# Sheet1.net
KiCad netlist of a schematic drawn in Altium Designer
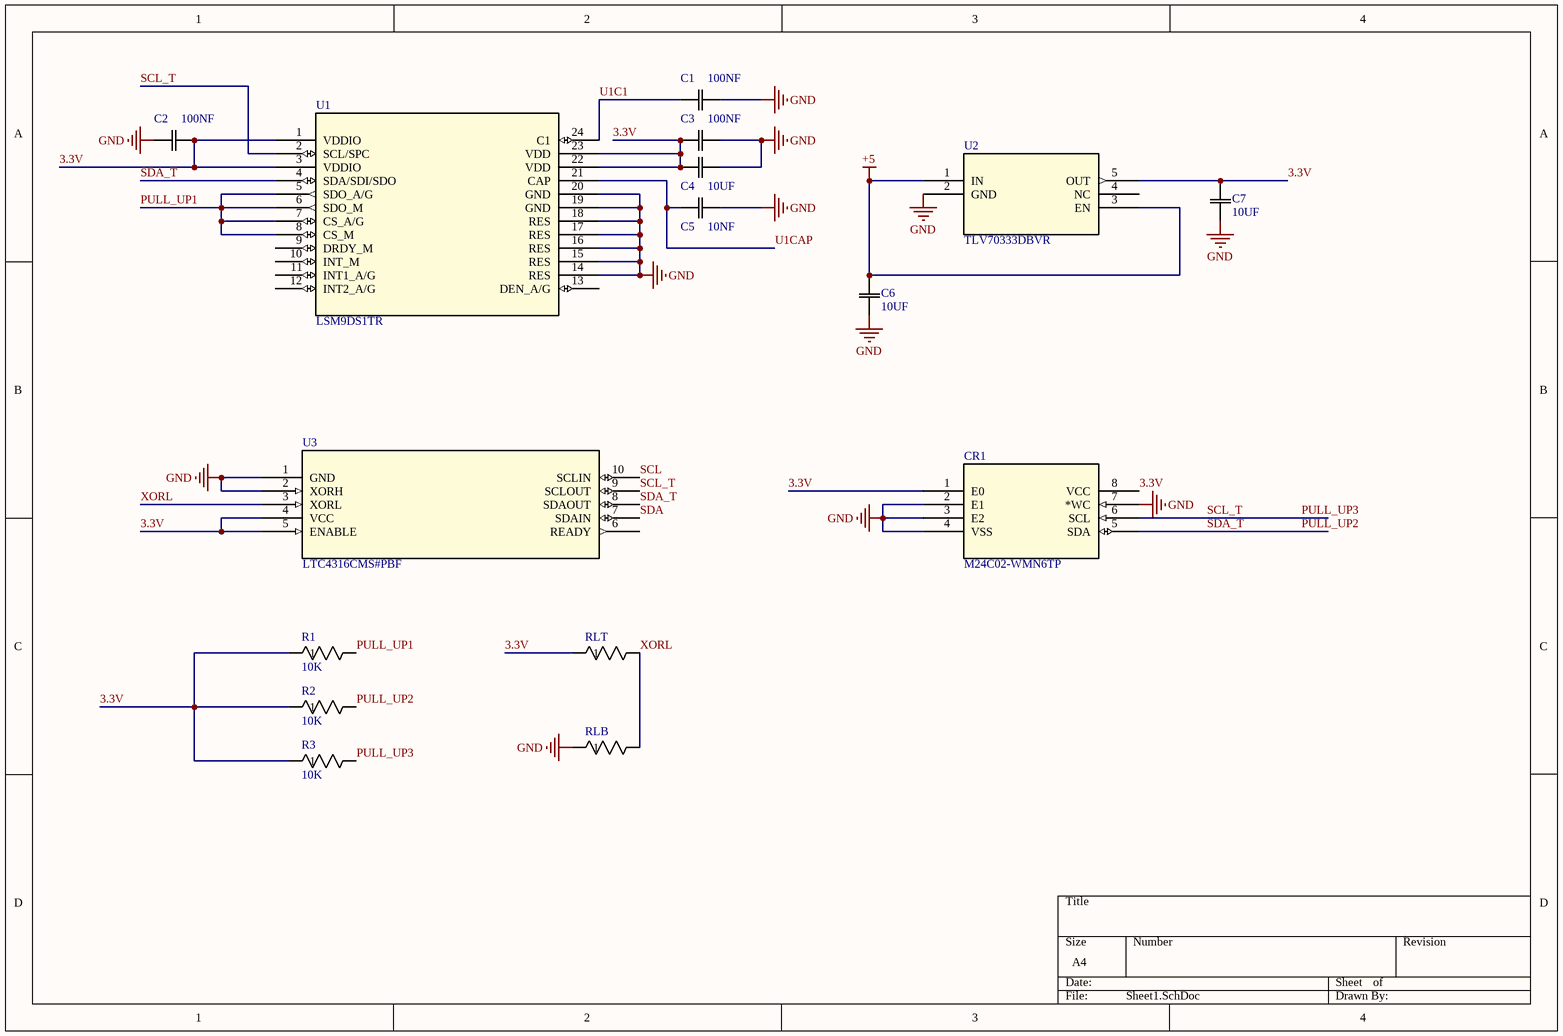
[diagram p0: Sheet1.SchDoc]

(export (version "E")
  (design (tool "Eeschema 10.0.6"))
  (components
    (comp (ref "C1")
      (value "100NF")
      (footprint "CC0603N_YAG")
      (description "No Description Available")
      (fields
        (field (name "MANUFACTURER_PART_NUMBER") "CC0603KRX7R9BB103")
        (field (name "COPYRIGHT") "Copyright (C) 2018 Accelerated Designs. All rights reserved")
      )
      (libsource (lib "0603 10nf") (part "CC0603KRX7R9BB103"))
    )
    (comp (ref "C2")
      (value "100NF")
      (footprint "CC0603N_YAG")
      (description "No Description Available")
      (fields
        (field (name "MANUFACTURER_PART_NUMBER") "CC0603KRX7R9BB103")
        (field (name "COPYRIGHT") "Copyright (C) 2018 Accelerated Designs. All rights reserved")
      )
      (libsource (lib "0603 10nf") (part "CC0603KRX7R9BB103"))
    )
    (comp (ref "C3")
      (value "100NF")
      (footprint "CC0603N_YAG")
      (description "No Description Available")
      (fields
        (field (name "MANUFACTURER_PART_NUMBER") "CC0603KRX7R9BB103")
        (field (name "COPYRIGHT") "Copyright (C) 2018 Accelerated Designs. All rights reserved")
      )
      (libsource (lib "0603 10nf") (part "CC0603KRX7R9BB103"))
    )
    (comp (ref "C4")
      (value "10UF")
      (footprint "CC0603N_YAG")
      (description "No Description Available")
      (fields
        (field (name "MANUFACTURER_PART_NUMBER") "CC0603KRX7R9BB103")
        (field (name "COPYRIGHT") "Copyright (C) 2018 Accelerated Designs. All rights reserved")
      )
      (libsource (lib "0603 10nf") (part "CC0603KRX7R9BB103"))
    )
    (comp (ref "C5")
      (value "10NF")
      (footprint "CC0603N_YAG")
      (description "No Description Available")
      (fields
        (field (name "MANUFACTURER_PART_NUMBER") "CC0603KRX7R9BB103")
        (field (name "COPYRIGHT") "Copyright (C) 2018 Accelerated Designs. All rights reserved")
      )
      (libsource (lib "0603 10nf") (part "CC0603KRX7R9BB103"))
    )
    (comp (ref "C6")
      (value "10UF")
      (footprint "CC0603N_YAG")
      (description "No Description Available")
      (fields
        (field (name "MANUFACTURER_PART_NUMBER") "CC0603KRX7R9BB103")
        (field (name "COPYRIGHT") "Copyright (C) 2018 Accelerated Designs. All rights reserved")
      )
      (libsource (lib "0603 10nf") (part "CC0603KRX7R9BB103"))
    )
    (comp (ref "C7")
      (value "10UF")
      (footprint "CC0603N_YAG")
      (description "No Description Available")
      (fields
        (field (name "MANUFACTURER_PART_NUMBER") "CC0603KRX7R9BB103")
        (field (name "COPYRIGHT") "Copyright (C) 2018 Accelerated Designs. All rights reserved")
      )
      (libsource (lib "0603 10nf") (part "CC0603KRX7R9BB103"))
    )
    (comp (ref "CR1")
      (value "M24C02-WMN6TP")
      (footprint "SO-8_STM")
      (description "No Description Available")
      (fields (field (name "COPYRIGHT") "Copyright (C) 2018 Accelerated Designs. All rights reserved"))
      (libsource (lib "M24C02-WMN6TP") (part "M24C02-WMN6TP"))
    )
    (comp (ref "R1")
      (value "10K")
      (footprint "0603_VIS")
      (description "No Description Available")
      (fields
        (field (name "MANUFACTURER_PART_NUMBER") "MCT0603MD1002DP500")
        (field (name "COPYRIGHT") "Copyright (C) 2018 Accelerated Designs. All rights reserved")
      )
      (libsource (lib "0603 10k") (part "MCT0603MD1002DP500"))
    )
    (comp (ref "R2")
      (value "10K")
      (footprint "0603_VIS")
      (description "No Description Available")
      (fields
        (field (name "MANUFACTURER_PART_NUMBER") "MCT0603MD1002DP500")
        (field (name "COPYRIGHT") "Copyright (C) 2018 Accelerated Designs. All rights reserved")
      )
      (libsource (lib "0603 10k") (part "MCT0603MD1002DP500"))
    )
    (comp (ref "R3")
      (value "10K")
      (footprint "0603_VIS")
      (description "No Description Available")
      (fields
        (field (name "MANUFACTURER_PART_NUMBER") "MCT0603MD1002DP500")
        (field (name "COPYRIGHT") "Copyright (C) 2018 Accelerated Designs. All rights reserved")
      )
      (libsource (lib "0603 10k") (part "MCT0603MD1002DP500"))
    )
    (comp (ref "RLB")
      (value "~")
      (footprint "0603_VIS")
      (description "No Description Available")
      (fields
        (field (name "MANUFACTURER_PART_NUMBER") "MCT0603MD1002DP500")
        (field (name "COPYRIGHT") "Copyright (C) 2018 Accelerated Designs. All rights reserved")
      )
      (libsource (lib "0603 10k") (part "MCT0603MD1002DP500"))
    )
    (comp (ref "RLT")
      (value "~")
      (footprint "0603_VIS")
      (description "No Description Available")
      (fields
        (field (name "MANUFACTURER_PART_NUMBER") "MCT0603MD1002DP500")
        (field (name "COPYRIGHT") "Copyright (C) 2018 Accelerated Designs. All rights reserved")
      )
      (libsource (lib "0603 10k") (part "MCT0603MD1002DP500"))
    )
    (comp (ref "U1")
      (value "LSM9DS1TR")
      (footprint "LGA-24_3X3P5X1_STM")
      (description "No Description Available")
      (fields (field (name "COPYRIGHT") "Copyright (C) 2018 Accelerated Designs. All rights reserved"))
      (libsource (lib "LSM9DSITR") (part "LSM9DS1TR"))
    )
    (comp (ref "U2")
      (value "TLV70333DBVR")
      (footprint "DBV5_TEX")
      (description "No Description Available")
      (fields (field (name "COPYRIGHT") "Copyright (C) 2018 Accelerated Designs. All rights reserved"))
      (libsource (lib "NCP114BSN330T1G") (part "TLV70333DBVR"))
    )
    (comp (ref "U3")
      (value "LTC4316CMS#PBF")
      (footprint "MSOP-10_MS_LIT")
      (description "No Description Available")
      (fields (field (name "COPYRIGHT") "Copyright (C) 2018 Accelerated Designs. All rights reserved"))
      (libsource (lib "LTC4316CMS#PBF") (part "LTC4316CMS#PBF"))
    )
  )
  (nets
    (net (code "1") (name "+5") (class "Default")
      (node (ref "C6") (pin "2") (pinfunction "2_2") (pintype "passive"))
      (node (ref "U2") (pin "1") (pinfunction "IN_1") (pintype "passive"))
      (node (ref "U2") (pin "3") (pinfunction "EN_3") (pintype "passive"))
    )
    (net (code "2") (name "/3.3V") (class "Default")
      (node (ref "C2") (pin "2") (pinfunction "2_2") (pintype "passive"))
      (node (ref "C3") (pin "1") (pinfunction "1_1") (pintype "passive"))
      (node (ref "C4") (pin "1") (pinfunction "1_1") (pintype "passive"))
      (node (ref "C7") (pin "2") (pinfunction "2_2") (pintype "passive"))
      (node (ref "CR1") (pin "1") (pinfunction "E0_1") (pintype "passive"))
      (node (ref "CR1") (pin "8") (pinfunction "VCC_8") (pintype "power_in"))
      (node (ref "R1") (pin "1") (pinfunction "1_1") (pintype "passive"))
      (node (ref "R2") (pin "1") (pinfunction "1_1") (pintype "passive"))
      (node (ref "R3") (pin "1") (pinfunction "1_1") (pintype "passive"))
      (node (ref "RLT") (pin "1") (pinfunction "1_1") (pintype "passive"))
      (node (ref "U1") (pin "1") (pinfunction "VDDIO_1") (pintype "power_in"))
      (node (ref "U1") (pin "22") (pinfunction "VDD_22") (pintype "power_in"))
      (node (ref "U1") (pin "23") (pinfunction "VDD_23") (pintype "power_in"))
      (node (ref "U1") (pin "3") (pinfunction "VDDIO_3") (pintype "power_in"))
      (node (ref "U2") (pin "5") (pinfunction "OUT_5") (pintype "output"))
      (node (ref "U3") (pin "4") (pinfunction "VCC_4") (pintype "power_in"))
      (node (ref "U3") (pin "5") (pinfunction "ENABLE_5") (pintype "input"))
    )
    (net (code "3") (name "/PULL_UP1") (class "Default")
      (node (ref "R1") (pin "2") (pinfunction "2_2") (pintype "passive"))
      (node (ref "U1") (pin "5") (pinfunction "SDO_A/G_5") (pintype "output"))
      (node (ref "U1") (pin "6") (pinfunction "SDO_M_6") (pintype "output"))
      (node (ref "U1") (pin "7") (pinfunction "CS_A/G_7") (pintype "bidirectional"))
      (node (ref "U1") (pin "8") (pinfunction "CS_M_8") (pintype "bidirectional"))
    )
    (net (code "4") (name "/PULL_UP2") (class "Default")
      (node (ref "CR1") (pin "5") (pinfunction "SDA_5") (pintype "bidirectional"))
      (node (ref "R2") (pin "2") (pinfunction "2_2") (pintype "passive"))
      (node (ref "U1") (pin "4") (pinfunction "SDA/SDI/SDO_4") (pintype "bidirectional"))
      (node (ref "U3") (pin "8") (pinfunction "SDAOUT_8") (pintype "bidirectional"))
    )
    (net (code "5") (name "/PULL_UP3") (class "Default")
      (node (ref "CR1") (pin "6") (pinfunction "SCL_6") (pintype "input"))
      (node (ref "R3") (pin "2") (pinfunction "2_2") (pintype "passive"))
      (node (ref "U1") (pin "2") (pinfunction "SCL/SPC_2") (pintype "bidirectional"))
      (node (ref "U3") (pin "9") (pinfunction "SCLOUT_9") (pintype "bidirectional"))
    )
    (net (code "6") (name "/SCL") (class "Default")
      (node (ref "U3") (pin "10") (pinfunction "SCLIN_10") (pintype "bidirectional"))
    )
    (net (code "7") (name "/SDA") (class "Default")
      (node (ref "U3") (pin "7") (pinfunction "SDAIN_7") (pintype "bidirectional"))
    )
    (net (code "8") (name "/U1C1") (class "Default")
      (node (ref "C1") (pin "1") (pinfunction "1_1") (pintype "passive"))
      (node (ref "U1") (pin "24") (pinfunction "C1_24") (pintype "bidirectional"))
    )
    (net (code "9") (name "/U1CAP") (class "Default")
      (node (ref "C5") (pin "1") (pinfunction "1_1") (pintype "passive"))
      (node (ref "U1") (pin "21") (pinfunction "CAP_21") (pintype "passive"))
    )
    (net (code "10") (name "/XORL") (class "Default")
      (node (ref "RLB") (pin "2") (pinfunction "2_2") (pintype "passive"))
      (node (ref "RLT") (pin "2") (pinfunction "2_2") (pintype "passive"))
      (node (ref "U3") (pin "3") (pinfunction "XORL_3") (pintype "input"))
    )
    (net (code "11") (name "GND") (class "Default")
      (node (ref "C1") (pin "2") (pinfunction "2_2") (pintype "passive"))
      (node (ref "C2") (pin "1") (pinfunction "1_1") (pintype "passive"))
      (node (ref "C3") (pin "2") (pinfunction "2_2") (pintype "passive"))
      (node (ref "C4") (pin "2") (pinfunction "2_2") (pintype "passive"))
      (node (ref "C5") (pin "2") (pinfunction "2_2") (pintype "passive"))
      (node (ref "C6") (pin "1") (pinfunction "1_1") (pintype "passive"))
      (node (ref "C7") (pin "1") (pinfunction "1_1") (pintype "passive"))
      (node (ref "CR1") (pin "2") (pinfunction "E1_2") (pintype "passive"))
      (node (ref "CR1") (pin "3") (pinfunction "E2_3") (pintype "passive"))
      (node (ref "CR1") (pin "4") (pinfunction "VSS_4") (pintype "power_in"))
      (node (ref "CR1") (pin "7") (pinfunction "*WC_7") (pintype "input"))
      (node (ref "RLB") (pin "1") (pinfunction "1_1") (pintype "passive"))
      (node (ref "U1") (pin "14") (pinfunction "RES_14") (pintype "passive"))
      (node (ref "U1") (pin "15") (pinfunction "RES_15") (pintype "passive"))
      (node (ref "U1") (pin "16") (pinfunction "RES_16") (pintype "passive"))
      (node (ref "U1") (pin "17") (pinfunction "RES_17") (pintype "passive"))
      (node (ref "U1") (pin "18") (pinfunction "RES_18") (pintype "passive"))
      (node (ref "U1") (pin "19") (pinfunction "GND_19") (pintype "power_in"))
      (node (ref "U1") (pin "20") (pinfunction "GND_20") (pintype "power_in"))
      (node (ref "U2") (pin "2") (pinfunction "GND_2") (pintype "passive"))
      (node (ref "U3") (pin "1") (pinfunction "GND_1") (pintype "power_in"))
      (node (ref "U3") (pin "2") (pinfunction "XORH_2") (pintype "input"))
    )
    (net (code "12") (name "unconnected-(U1-DEN_A{slash}G-Pad13)") (class "Default")
      (node (ref "U1") (pin "13") (pinfunction "DEN_A/G_13") (pintype "bidirectional"))
    )
    (net (code "13") (name "unconnected-(U1-DRDY_M-Pad9)") (class "Default")
      (node (ref "U1") (pin "9") (pinfunction "DRDY_M_9") (pintype "bidirectional"))
    )
    (net (code "14") (name "unconnected-(U1-INT1_A{slash}G-Pad11)") (class "Default")
      (node (ref "U1") (pin "11") (pinfunction "INT1_A/G_11") (pintype "bidirectional"))
    )
    (net (code "15") (name "unconnected-(U1-INT2_A{slash}G-Pad12)") (class "Default")
      (node (ref "U1") (pin "12") (pinfunction "INT2_A/G_12") (pintype "bidirectional"))
    )
    (net (code "16") (name "unconnected-(U1-INT_M-Pad10)") (class "Default")
      (node (ref "U1") (pin "10") (pinfunction "INT_M_10") (pintype "bidirectional"))
    )
    (net (code "17") (name "unconnected-(U2-NC-Pad4)") (class "Default")
      (node (ref "U2") (pin "4") (pinfunction "NC_4") (pintype "passive"))
    )
    (net (code "18") (name "unconnected-(U3-READY-Pad6)") (class "Default")
      (node (ref "U3") (pin "6") (pinfunction "READY_6") (pintype "output"))
    )
  )
)
